# PRA_25_4_23_1.net
KiCad netlist of a schematic drawn in EAGLE
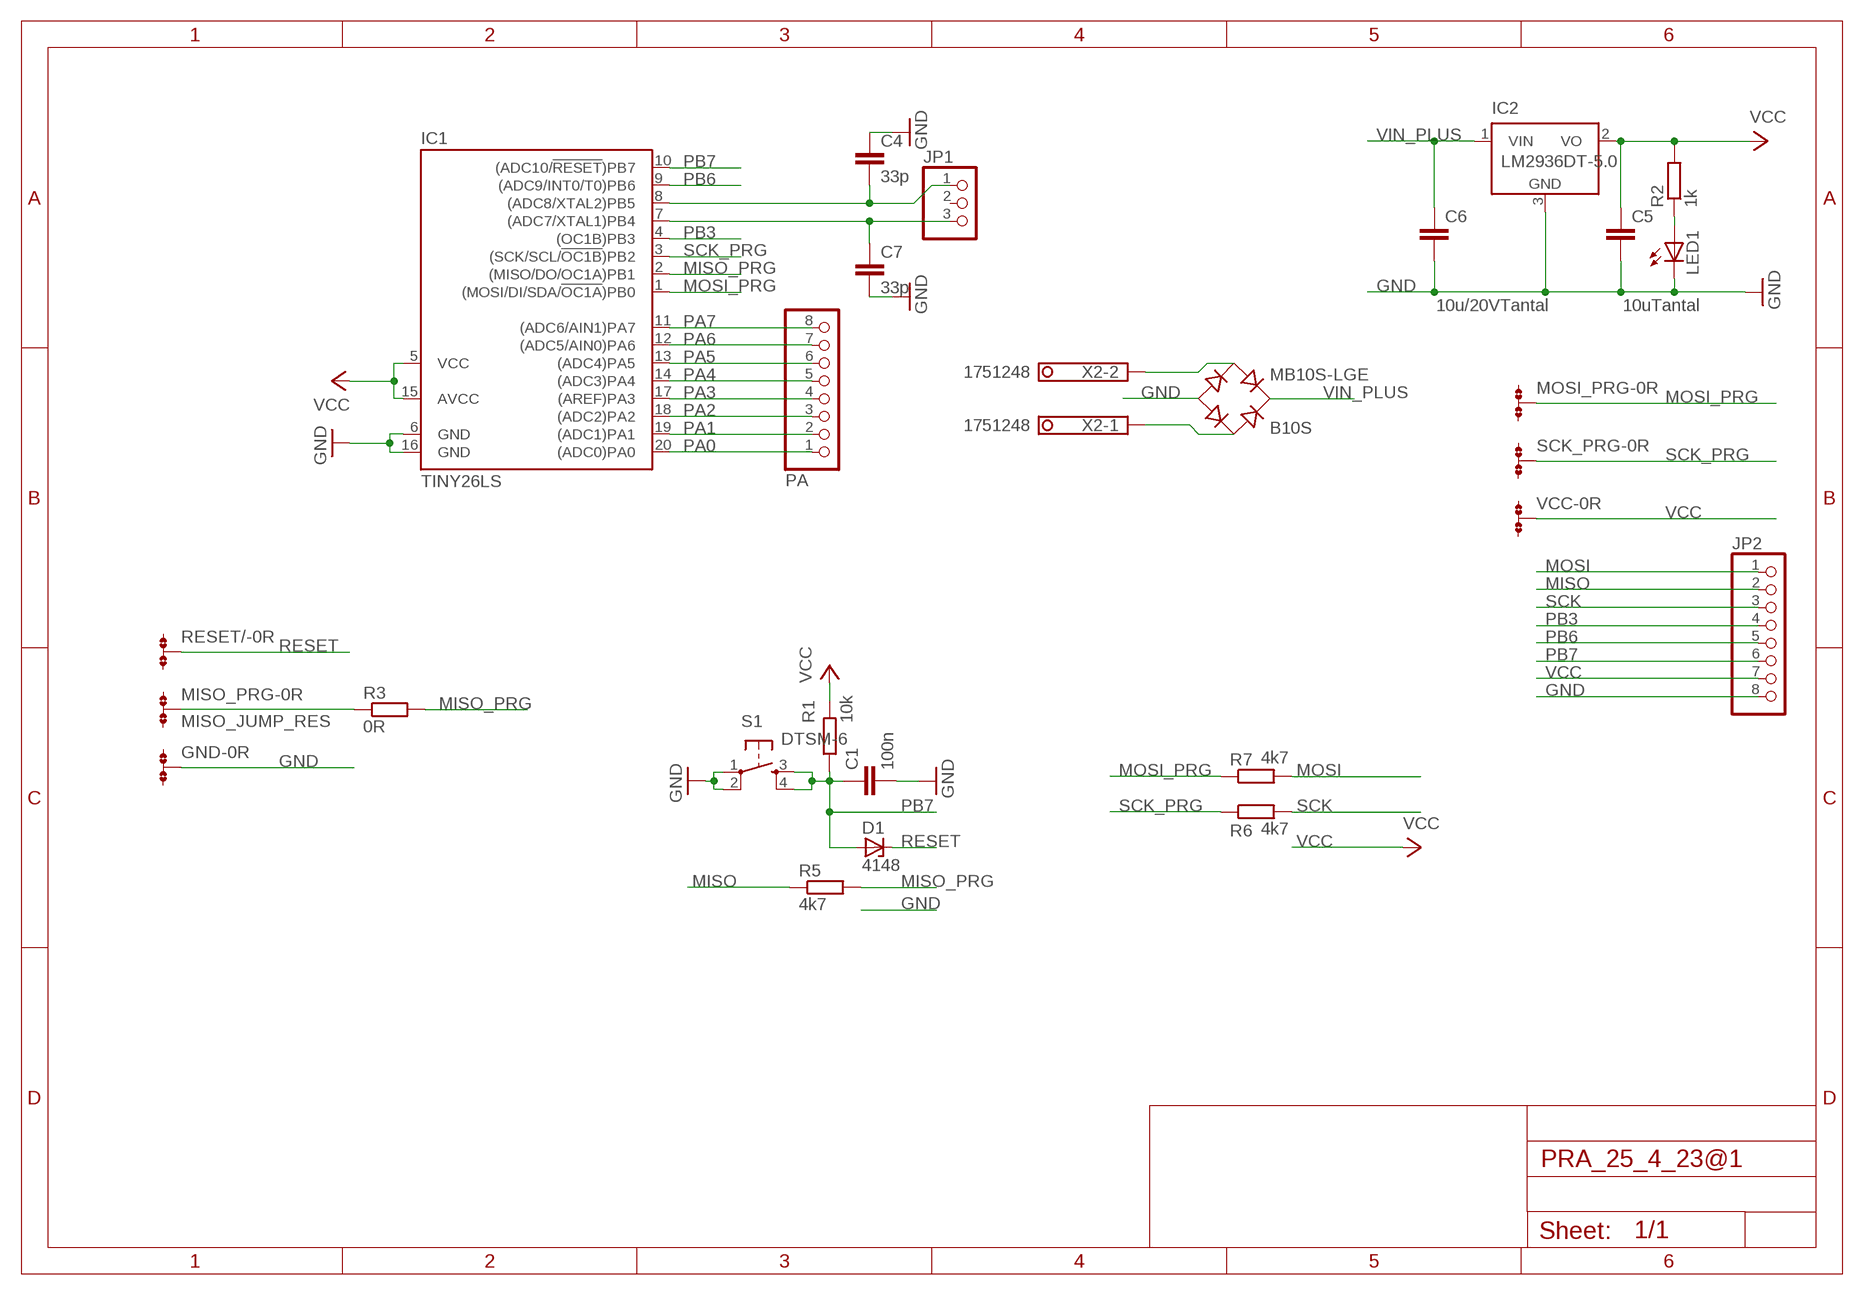
[diagram p0: schematic, sheet 1]

(export (version "E")
  (design (tool "Eeschema 10.0.6"))
  (components
    (comp (ref "C1")
      (value "100n")
      (footprint "eagle-import:C1206")
      (libsource (lib "eagle-import") (part "C-EUC1206"))
    )
    (comp (ref "C4")
      (value "33p")
      (footprint "eagle-import:C1206")
      (libsource (lib "eagle-import") (part "C-EUC1206"))
    )
    (comp (ref "C5")
      (value "10uTantal")
      (footprint "eagle-import:C1206K")
      (libsource (lib "eagle-import") (part "C-EUC1206K"))
    )
    (comp (ref "C6")
      (value "10u/20VTantal")
      (footprint "eagle-import:C1206K")
      (libsource (lib "eagle-import") (part "C-EUC1206K"))
    )
    (comp (ref "C7")
      (value "33p")
      (footprint "eagle-import:C1206")
      (libsource (lib "eagle-import") (part "C-EUC1206"))
    )
    (comp (ref "D1")
      (value "4148")
      (footprint "eagle-import:SMB")
      (libsource (lib "eagle-import") (part "ZENER-DIODESMB"))
    )
    (comp (ref "GND")
      (value "0R-JUMPA")
      (footprint "eagle-import:A0R-JMP")
      (libsource (lib "eagle-import") (part "0R-JUMPA"))
    )
    (comp (ref "IC1")
      (value "TINY26LS")
      (footprint "eagle-import:SO20L")
      (fields (field (name "MPN") "ATTINY26L-8SU"))
      (libsource (lib "eagle-import") (part "TINY26SL"))
    )
    (comp (ref "IC2")
      (value "LM2936DT-5.0")
      (footprint "eagle-import:TO252")
      (fields (field (name "MF") "NATIONAL SEMICONDUCTOR") (field (name "MPN") "LM2936DT-5.0/NOPB"))
      (libsource (lib "eagle-import") (part "LM2936?DT-5.0"))
    )
    (comp (ref "JP1")
      (value "PINHD-1X3")
      (footprint "eagle-import:1X03")
      (libsource (lib "eagle-import") (part "PINHD-1X3"))
    )
    (comp (ref "JP2")
      (value "PINHD-1X8/90")
      (footprint "eagle-import:1X08_90")
      (libsource (lib "eagle-import") (part "PINHD-1X8/90"))
    )
    (comp (ref "LED1")
      (value "LEDSMT1206")
      (footprint "eagle-import:1206")
      (libsource (lib "eagle-import") (part "LEDSMT1206"))
    )
    (comp (ref "MB10S-LGE")
      (value "B10S")
      (footprint "eagle-import:MBS")
      (libsource (lib "eagle-import") (part "BS10"))
    )
    (comp (ref "MISO_PRG")
      (value "0R-JUMPA")
      (footprint "eagle-import:A0R-JMP")
      (libsource (lib "eagle-import") (part "0R-JUMPA"))
    )
    (comp (ref "MOSI_PRG")
      (value "0R-JUMPA")
      (footprint "eagle-import:A0R-JMP")
      (libsource (lib "eagle-import") (part "0R-JUMPA"))
    )
    (comp (ref "PA")
      (value "PINHD-1X8/90")
      (footprint "eagle-import:1X08_90")
      (libsource (lib "eagle-import") (part "PINHD-1X8/90"))
    )
    (comp (ref "R1")
      (value "10k")
      (footprint "eagle-import:R1206")
      (libsource (lib "eagle-import") (part "R-EU_R1206"))
    )
    (comp (ref "R2")
      (value "1k")
      (footprint "eagle-import:R1206")
      (libsource (lib "eagle-import") (part "R-EU_R1206"))
    )
    (comp (ref "R3")
      (value "0R")
      (footprint "eagle-import:M1406")
      (libsource (lib "eagle-import") (part "R-EU_M1406"))
    )
    (comp (ref "R5")
      (value "4k7")
      (footprint "eagle-import:R1206")
      (libsource (lib "eagle-import") (part "R-EU_R1206"))
    )
    (comp (ref "R6")
      (value "4k7")
      (footprint "eagle-import:R1206")
      (libsource (lib "eagle-import") (part "R-EU_R1206"))
    )
    (comp (ref "R7")
      (value "4k7")
      (footprint "eagle-import:R1206")
      (libsource (lib "eagle-import") (part "R-EU_R1206"))
    )
    (comp (ref "RESET/")
      (value "0R-JUMPA")
      (footprint "eagle-import:A0R-JMP")
      (libsource (lib "eagle-import") (part "0R-JUMPA"))
    )
    (comp (ref "S1")
      (value "DTSM-6")
      (footprint "eagle-import:DTSM-6")
      (libsource (lib "eagle-import") (part "DTSM-6"))
    )
    (comp (ref "SCK_PRG")
      (value "0R-JUMPA")
      (footprint "eagle-import:A0R-JMP")
      (libsource (lib "eagle-import") (part "0R-JUMPA"))
    )
    (comp (ref "VCC")
      (value "0R-JUMPA")
      (footprint "eagle-import:A0R-JMP")
      (libsource (lib "eagle-import") (part "0R-JUMPA"))
    )
    (comp (ref "X2")
      (value "1751248")
      (footprint "eagle-import:1751248")
      (libsource (lib "eagle-import") (part "1751248"))
    )
  )
  (nets
    (net (code "1") (name "/MISO") (class "Default")
      (node (ref "JP2") (pin "2") (pinfunction "2_2") (pintype "passive"))
      (node (ref "R5") (pin "1") (pinfunction "1_1") (pintype "passive"))
    )
    (net (code "2") (name "/MISO_JUMP_RES") (class "Default")
      (node (ref "MISO_PRG") (pin "2") (pinfunction "2_2") (pintype "passive"))
      (node (ref "R3") (pin "1") (pinfunction "1_1") (pintype "passive"))
    )
    (net (code "3") (name "/MISO_PRG") (class "Default")
      (node (ref "IC1") (pin "2") (pinfunction "(MISO/DO/OC1A)PB1_2") (pintype "bidirectional"))
      (node (ref "R3") (pin "2") (pinfunction "2_2") (pintype "passive"))
      (node (ref "R5") (pin "2") (pinfunction "2_2") (pintype "passive"))
    )
    (net (code "4") (name "/MOSI") (class "Default")
      (node (ref "JP2") (pin "1") (pinfunction "1_1") (pintype "passive"))
      (node (ref "R7") (pin "2") (pinfunction "2_2") (pintype "passive"))
    )
    (net (code "5") (name "/MOSI_PRG") (class "Default")
      (node (ref "IC1") (pin "1") (pinfunction "(MOSI/DI/SDA/~{OC1A})PB0_1") (pintype "bidirectional"))
      (node (ref "MOSI_PRG") (pin "2") (pinfunction "2_2") (pintype "passive"))
      (node (ref "R7") (pin "1") (pinfunction "1_1") (pintype "passive"))
    )
    (net (code "6") (name "/PA0") (class "Default")
      (node (ref "IC1") (pin "20") (pinfunction "(ADC0)PA0_20") (pintype "bidirectional"))
      (node (ref "PA") (pin "1") (pinfunction "1_1") (pintype "passive"))
    )
    (net (code "7") (name "/PA1") (class "Default")
      (node (ref "IC1") (pin "19") (pinfunction "(ADC1)PA1_19") (pintype "bidirectional"))
      (node (ref "PA") (pin "2") (pinfunction "2_2") (pintype "passive"))
    )
    (net (code "8") (name "/PA2") (class "Default")
      (node (ref "IC1") (pin "18") (pinfunction "(ADC2)PA2_18") (pintype "bidirectional"))
      (node (ref "PA") (pin "3") (pinfunction "3_3") (pintype "passive"))
    )
    (net (code "9") (name "/PA3") (class "Default")
      (node (ref "IC1") (pin "17") (pinfunction "(AREF)PA3_17") (pintype "bidirectional"))
      (node (ref "PA") (pin "4") (pinfunction "4_4") (pintype "passive"))
    )
    (net (code "10") (name "/PA4") (class "Default")
      (node (ref "IC1") (pin "14") (pinfunction "(ADC3)PA4_14") (pintype "bidirectional"))
      (node (ref "PA") (pin "5") (pinfunction "5_5") (pintype "passive"))
    )
    (net (code "11") (name "/PA5") (class "Default")
      (node (ref "IC1") (pin "13") (pinfunction "(ADC4)PA5_13") (pintype "bidirectional"))
      (node (ref "PA") (pin "6") (pinfunction "6_6") (pintype "passive"))
    )
    (net (code "12") (name "/PA6") (class "Default")
      (node (ref "IC1") (pin "12") (pinfunction "(ADC5/AIN0)PA6_12") (pintype "bidirectional"))
      (node (ref "PA") (pin "7") (pinfunction "7_7") (pintype "passive"))
    )
    (net (code "13") (name "/PA7") (class "Default")
      (node (ref "IC1") (pin "11") (pinfunction "(ADC6/AIN1)PA7_11") (pintype "bidirectional"))
      (node (ref "PA") (pin "8") (pinfunction "8_8") (pintype "passive"))
    )
    (net (code "14") (name "/PB3") (class "Default")
      (node (ref "IC1") (pin "4") (pinfunction "(OC1B)PB3_4") (pintype "bidirectional"))
      (node (ref "JP2") (pin "4") (pinfunction "4_4") (pintype "passive"))
    )
    (net (code "15") (name "/PB6") (class "Default")
      (node (ref "IC1") (pin "9") (pinfunction "(ADC9/INT0/T0)PB6_9") (pintype "bidirectional"))
      (node (ref "JP2") (pin "5") (pinfunction "5_5") (pintype "passive"))
    )
    (net (code "16") (name "/PB7") (class "Default")
      (node (ref "C1") (pin "1") (pinfunction "1_1") (pintype "passive"))
      (node (ref "D1") (pin "A") (pinfunction "A_A") (pintype "passive"))
      (node (ref "IC1") (pin "10") (pinfunction "(ADC10/~{RESET})PB7_10") (pintype "bidirectional"))
      (node (ref "JP2") (pin "6") (pinfunction "6_6") (pintype "passive"))
      (node (ref "R1") (pin "1") (pinfunction "1_1") (pintype "passive"))
      (node (ref "S1") (pin "3") (pinfunction "3_3") (pintype "passive"))
      (node (ref "S1") (pin "4") (pinfunction "4_4") (pintype "passive"))
    )
    (net (code "17") (name "/RESET") (class "Default")
      (node (ref "D1") (pin "C") (pinfunction "C_C") (pintype "passive"))
      (node (ref "RESET/") (pin "2") (pinfunction "2_2") (pintype "passive"))
    )
    (net (code "18") (name "/SCK") (class "Default")
      (node (ref "JP2") (pin "3") (pinfunction "3_3") (pintype "passive"))
      (node (ref "R6") (pin "2") (pinfunction "2_2") (pintype "passive"))
    )
    (net (code "19") (name "/SCK_PRG") (class "Default")
      (node (ref "IC1") (pin "3") (pinfunction "(SCK/SCL/~{OC1B})PB2_3") (pintype "bidirectional"))
      (node (ref "R6") (pin "1") (pinfunction "1_1") (pintype "passive"))
      (node (ref "SCK_PRG") (pin "2") (pinfunction "2_2") (pintype "passive"))
    )
    (net (code "20") (name "/VIN_PLUS") (class "Default")
      (node (ref "C6") (pin "1") (pinfunction "1_1") (pintype "passive"))
      (node (ref "IC2") (pin "1") (pinfunction "VIN_1") (pintype "input"))
      (node (ref "MB10S-LGE") (pin "+") (pinfunction "+_+") (pintype "passive"))
    )
    (net (code "21") (name "GND") (class "Default")
      (node (ref "C1") (pin "2") (pinfunction "2_2") (pintype "passive"))
      (node (ref "C4") (pin "1") (pinfunction "1_1") (pintype "passive"))
      (node (ref "C5") (pin "2") (pinfunction "2_2") (pintype "passive"))
      (node (ref "C6") (pin "2") (pinfunction "2_2") (pintype "passive"))
      (node (ref "C7") (pin "2") (pinfunction "2_2") (pintype "passive"))
      (node (ref "GND") (pin "2") (pinfunction "2_2") (pintype "passive"))
      (node (ref "IC1") (pin "16") (pinfunction "GND_16") (pintype "power_in"))
      (node (ref "IC1") (pin "6") (pinfunction "GND_6") (pintype "power_in"))
      (node (ref "IC2") (pin "3") (pinfunction "GND_3") (pintype "passive"))
      (node (ref "JP2") (pin "8") (pinfunction "8_8") (pintype "passive"))
      (node (ref "LED1") (pin "C") (pinfunction "C_C") (pintype "passive"))
      (node (ref "MB10S-LGE") (pin "-") (pinfunction "-_-") (pintype "passive"))
      (node (ref "S1") (pin "1") (pinfunction "1_1") (pintype "passive"))
      (node (ref "S1") (pin "2") (pinfunction "2_2") (pintype "passive"))
    )
    (net (code "22") (name "Net-(IC1-(ADC7{slash}XTAL1)PB4)") (class "Default")
      (node (ref "C7") (pin "1") (pinfunction "1_1") (pintype "passive"))
      (node (ref "IC1") (pin "7") (pinfunction "(ADC7/XTAL1)PB4_7") (pintype "bidirectional"))
      (node (ref "JP1") (pin "3") (pinfunction "3_3") (pintype "passive"))
    )
    (net (code "23") (name "Net-(IC1-(ADC8{slash}XTAL2)PB5)") (class "Default")
      (node (ref "C4") (pin "2") (pinfunction "2_2") (pintype "passive"))
      (node (ref "IC1") (pin "8") (pinfunction "(ADC8/XTAL2)PB5_8") (pintype "bidirectional"))
      (node (ref "JP1") (pin "1") (pinfunction "1_1") (pintype "passive"))
    )
    (net (code "24") (name "Net-(LED1-PadA)") (class "Default")
      (node (ref "LED1") (pin "A") (pinfunction "A_A") (pintype "passive"))
      (node (ref "R2") (pin "1") (pinfunction "1_1") (pintype "passive"))
    )
    (net (code "25") (name "Net-(X2A-K)") (class "Default")
      (node (ref "MB10S-LGE") (pin "AC2") (pinfunction "AC2_AC2") (pintype "passive"))
      (node (ref "X2") (pin "1") (pinfunction "K_1") (pintype "passive"))
    )
    (net (code "26") (name "Net-(X2B-K)") (class "Default")
      (node (ref "MB10S-LGE") (pin "AC1") (pinfunction "AC1_AC1") (pintype "passive"))
      (node (ref "X2") (pin "2") (pinfunction "K_2") (pintype "passive"))
    )
    (net (code "27") (name "VCC") (class "Default")
      (node (ref "C5") (pin "1") (pinfunction "1_1") (pintype "passive"))
      (node (ref "IC1") (pin "15") (pinfunction "AVCC_15") (pintype "power_in"))
      (node (ref "IC1") (pin "5") (pinfunction "VCC_5") (pintype "power_in"))
      (node (ref "IC2") (pin "2") (pinfunction "VO_2") (pintype "passive"))
      (node (ref "JP2") (pin "7") (pinfunction "7_7") (pintype "passive"))
      (node (ref "R1") (pin "2") (pinfunction "2_2") (pintype "passive"))
      (node (ref "R2") (pin "2") (pinfunction "2_2") (pintype "passive"))
      (node (ref "VCC") (pin "2") (pinfunction "2_2") (pintype "passive"))
    )
    (net (code "28") (name "unconnected-(GND-Pad1)") (class "Default")
      (node (ref "GND") (pin "1") (pinfunction "1_1") (pintype "passive"))
    )
    (net (code "29") (name "unconnected-(GND-Pad3)") (class "Default")
      (node (ref "GND") (pin "3") (pinfunction "3_3") (pintype "passive"))
    )
    (net (code "30") (name "unconnected-(JP1-Pad2)") (class "Default")
      (node (ref "JP1") (pin "2") (pinfunction "2_2") (pintype "passive"))
    )
    (net (code "31") (name "unconnected-(MISO_PRG-Pad1)") (class "Default")
      (node (ref "MISO_PRG") (pin "1") (pinfunction "1_1") (pintype "passive"))
    )
    (net (code "32") (name "unconnected-(MISO_PRG-Pad3)") (class "Default")
      (node (ref "MISO_PRG") (pin "3") (pinfunction "3_3") (pintype "passive"))
    )
    (net (code "33") (name "unconnected-(MOSI_PRG-Pad1)") (class "Default")
      (node (ref "MOSI_PRG") (pin "1") (pinfunction "1_1") (pintype "passive"))
    )
    (net (code "34") (name "unconnected-(MOSI_PRG-Pad3)") (class "Default")
      (node (ref "MOSI_PRG") (pin "3") (pinfunction "3_3") (pintype "passive"))
    )
    (net (code "35") (name "unconnected-(RESET/-Pad1)") (class "Default")
      (node (ref "RESET/") (pin "1") (pinfunction "1_1") (pintype "passive"))
    )
    (net (code "36") (name "unconnected-(RESET/-Pad3)") (class "Default")
      (node (ref "RESET/") (pin "3") (pinfunction "3_3") (pintype "passive"))
    )
    (net (code "37") (name "unconnected-(SCK_PRG-Pad1)") (class "Default")
      (node (ref "SCK_PRG") (pin "1") (pinfunction "1_1") (pintype "passive"))
    )
    (net (code "38") (name "unconnected-(SCK_PRG-Pad3)") (class "Default")
      (node (ref "SCK_PRG") (pin "3") (pinfunction "3_3") (pintype "passive"))
    )
    (net (code "39") (name "unconnected-(VCC-Pad1)") (class "Default")
      (node (ref "VCC") (pin "1") (pinfunction "1_1") (pintype "passive"))
    )
    (net (code "40") (name "unconnected-(VCC-Pad3)") (class "Default")
      (node (ref "VCC") (pin "3") (pinfunction "3_3") (pintype "passive"))
    )
  )
)
